# PIC_Schematic.net
KiCad netlist of a schematic drawn in Altium Designer
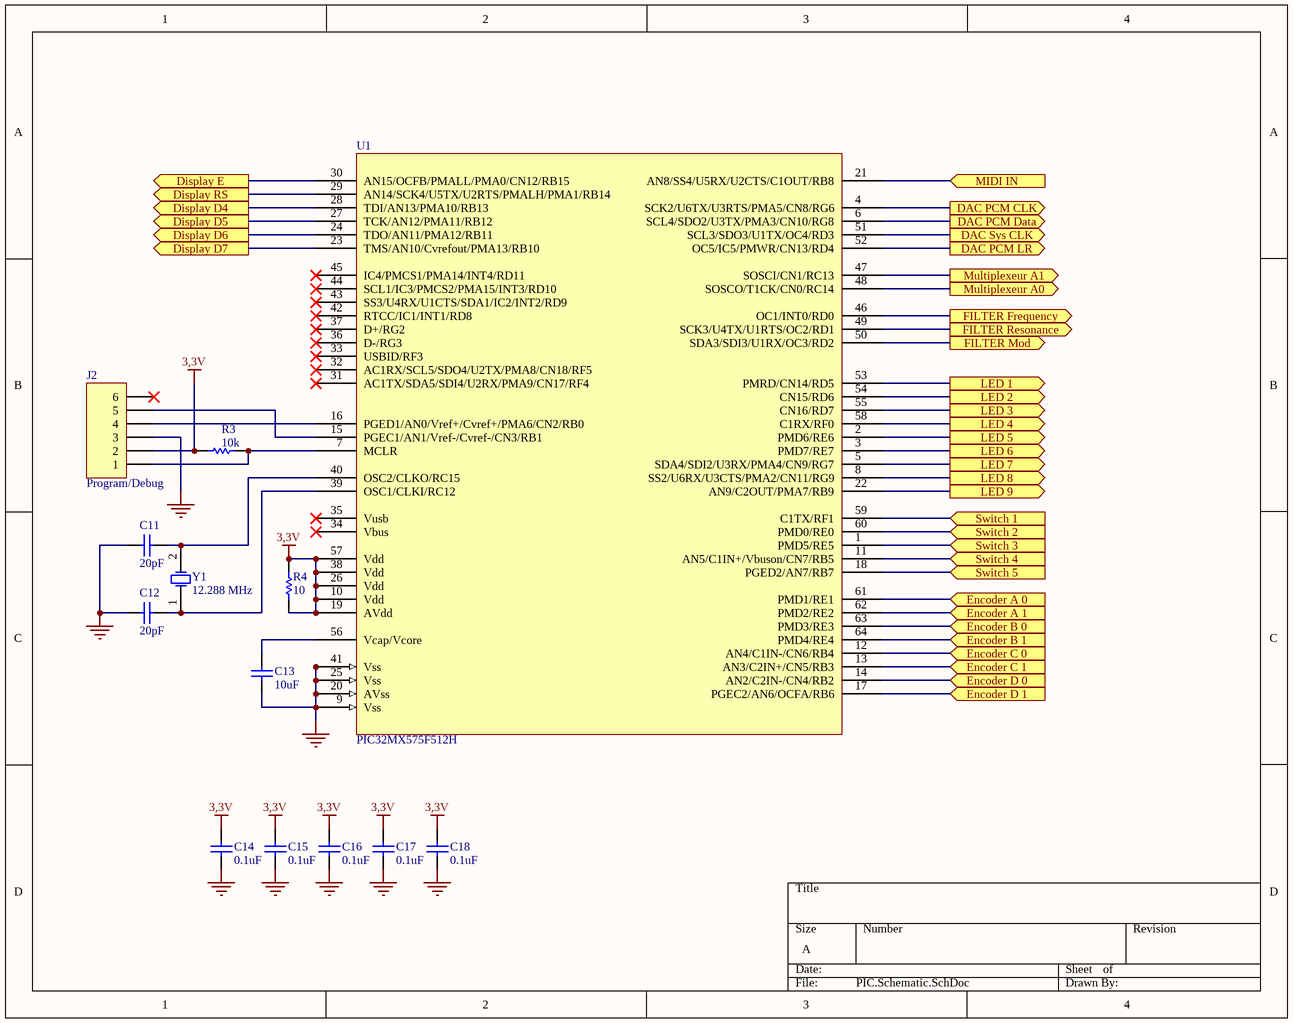
[diagram p0: PIC.Schematic.SchDoc]

(export (version "E")
  (design (tool "Eeschema 10.0.6"))
  (components
    (comp (ref "C11")
      (value "20pF")
      (footprint "CAPC1608N")
      (description "Capacitor (Semiconductor SIM Model)")
      (fields (field (name "PUBLISHER") "Altium Limited"))
      (libsource (lib "Miscellaneous Devices") (part "Cap Semi"))
    )
    (comp (ref "C12")
      (value "20pF")
      (footprint "CAPC1608N")
      (description "Capacitor (Semiconductor SIM Model)")
      (fields (field (name "PUBLISHER") "Altium Limited"))
      (libsource (lib "Miscellaneous Devices") (part "Cap Semi"))
    )
    (comp (ref "C13")
      (value "10uF")
      (footprint "RAD-0.3")
      (description "Capacitor")
      (fields (field (name "PUBLISHER") "Altium Limited"))
      (libsource (lib "Miscellaneous Devices") (part "Cap"))
    )
    (comp (ref "C14")
      (value "0.1uF")
      (footprint "CAPC1608N")
      (description "Capacitor (Semiconductor SIM Model)")
      (fields (field (name "PUBLISHER") "Altium Limited"))
      (libsource (lib "Miscellaneous Devices") (part "Cap Semi"))
    )
    (comp (ref "C15")
      (value "0.1uF")
      (footprint "CAPC1608N")
      (description "Capacitor (Semiconductor SIM Model)")
      (fields (field (name "PUBLISHER") "Altium Limited"))
      (libsource (lib "Miscellaneous Devices") (part "Cap Semi"))
    )
    (comp (ref "C16")
      (value "0.1uF")
      (footprint "CAPC1608N")
      (description "Capacitor (Semiconductor SIM Model)")
      (fields (field (name "PUBLISHER") "Altium Limited"))
      (libsource (lib "Miscellaneous Devices") (part "Cap Semi"))
    )
    (comp (ref "C17")
      (value "0.1uF")
      (footprint "CAPC1608N")
      (description "Capacitor (Semiconductor SIM Model)")
      (fields (field (name "PUBLISHER") "Altium Limited"))
      (libsource (lib "Miscellaneous Devices") (part "Cap Semi"))
    )
    (comp (ref "C18")
      (value "0.1uF")
      (footprint "CAPC1608N")
      (description "Capacitor (Semiconductor SIM Model)")
      (fields (field (name "PUBLISHER") "Altium Limited"))
      (libsource (lib "Miscellaneous Devices") (part "Cap Semi"))
    )
    (comp (ref "J2")
      (value "Program/Debug")
      (footprint "RJ11")
      (description "Header, 6-Pin, Right Angle")
      (fields (field (name "PUBLISHER") "Altium Limited"))
      (libsource (lib "Miscellaneous Connectors") (part "Header 6H"))
    )
    (comp (ref "R3")
      (value "10k")
      (footprint "CAPC1608N")
      (description "Resistor")
      (fields (field (name "PUBLISHER") "Altium Limited"))
      (libsource (lib "Miscellaneous Devices") (part "Res1"))
    )
    (comp (ref "R4")
      (value "10")
      (footprint "CAPC1608N")
      (description "Resistor")
      (fields (field (name "PUBLISHER") "Altium Limited"))
      (libsource (lib "Miscellaneous Devices") (part "Res1"))
    )
    (comp (ref "U1")
      (value "PIC32MX575F512H")
      (footprint "PIC32")
      (libsource (lib "SynthyTwo.Components") (part "PIC32 MX575F512H"))
    )
    (comp (ref "Y1")
      (value "12.288 MHz")
      (footprint "Xtal")
      (description "Crystal Oscillator")
      (fields (field (name "PUBLISHER") "Altium Limited"))
      (libsource (lib "Miscellaneous Devices") (part "XTAL"))
    )
  )
  (nets
    (net (code "1") (name "/DAC PCM CLK") (class "Default")
      (node (ref "U1") (pin "4") (pinfunction "SCK2/U6TX/U3RTS/PMA5/CN8/RG6_4") (pintype "passive"))
    )
    (net (code "2") (name "/DAC PCM Data") (class "Default")
      (node (ref "U1") (pin "6") (pinfunction "SCL4/SDO2/U3TX/PMA3/CN10/RG8_6") (pintype "passive"))
    )
    (net (code "3") (name "/DAC PCM LR") (class "Default")
      (node (ref "U1") (pin "52") (pinfunction "OC5/IC5/PMWR/CN13/RD4_52") (pintype "passive"))
    )
    (net (code "4") (name "/DAC Sys CLK") (class "Default")
      (node (ref "U1") (pin "51") (pinfunction "SCL3/SDO3/U1TX/OC4/RD3_51") (pintype "passive"))
    )
    (net (code "5") (name "/Display D4") (class "Default")
      (node (ref "U1") (pin "28") (pinfunction "TDI/AN13/PMA10/RB13_28") (pintype "passive"))
    )
    (net (code "6") (name "/Display D5") (class "Default")
      (node (ref "U1") (pin "27") (pinfunction "TCK/AN12/PMA11/RB12_27") (pintype "passive"))
    )
    (net (code "7") (name "/Display D6") (class "Default")
      (node (ref "U1") (pin "24") (pinfunction "TDO/AN11/PMA12/RB11_24") (pintype "passive"))
    )
    (net (code "8") (name "/Display D7") (class "Default")
      (node (ref "U1") (pin "23") (pinfunction "TMS/AN10/Cvrefout/PMA13/RB10_23") (pintype "passive"))
    )
    (net (code "9") (name "/Display E") (class "Default")
      (node (ref "U1") (pin "30") (pinfunction "AN15/OCFB/PMALL/PMA0/CN12/RB15_30") (pintype "passive"))
    )
    (net (code "10") (name "/Display RS") (class "Default")
      (node (ref "U1") (pin "29") (pinfunction "AN14/SCK4/U5TX/U2RTS/PMALH/PMA1/RB14_29") (pintype "passive"))
    )
    (net (code "11") (name "/Encoder A 0") (class "Default")
      (node (ref "U1") (pin "61") (pinfunction "PMD1/RE1_61") (pintype "passive"))
    )
    (net (code "12") (name "/Encoder A 1") (class "Default")
      (node (ref "U1") (pin "62") (pinfunction "PMD2/RE2_62") (pintype "passive"))
    )
    (net (code "13") (name "/Encoder B 0") (class "Default")
      (node (ref "U1") (pin "63") (pinfunction "PMD3/RE3_63") (pintype "passive"))
    )
    (net (code "14") (name "/Encoder B 1") (class "Default")
      (node (ref "U1") (pin "64") (pinfunction "PMD4/RE4_64") (pintype "passive"))
    )
    (net (code "15") (name "/Encoder C 0") (class "Default")
      (node (ref "U1") (pin "12") (pinfunction "AN4/C1IN-/CN6/RB4_12") (pintype "passive"))
    )
    (net (code "16") (name "/Encoder C 1") (class "Default")
      (node (ref "U1") (pin "13") (pinfunction "AN3/C2IN+/CN5/RB3_13") (pintype "passive"))
    )
    (net (code "17") (name "/Encoder D 0") (class "Default")
      (node (ref "U1") (pin "14") (pinfunction "AN2/C2IN-/CN4/RB2_14") (pintype "passive"))
    )
    (net (code "18") (name "/Encoder D 1") (class "Default")
      (node (ref "U1") (pin "17") (pinfunction "PGEC2/AN6/OCFA/RB6_17") (pintype "passive"))
    )
    (net (code "19") (name "/FILTER Frequency") (class "Default")
      (node (ref "U1") (pin "46") (pinfunction "OC1/INT0/RD0_46") (pintype "passive"))
    )
    (net (code "20") (name "/FILTER Mod") (class "Default")
      (node (ref "U1") (pin "50") (pinfunction "SDA3/SDI3/U1RX/OC3/RD2_50") (pintype "passive"))
    )
    (net (code "21") (name "/FILTER Resonance") (class "Default")
      (node (ref "U1") (pin "49") (pinfunction "SCK3/U4TX/U1RTS/OC2/RD1_49") (pintype "passive"))
    )
    (net (code "22") (name "/LED 1") (class "Default")
      (node (ref "U1") (pin "53") (pinfunction "PMRD/CN14/RD5_53") (pintype "passive"))
    )
    (net (code "23") (name "/LED 2") (class "Default")
      (node (ref "U1") (pin "54") (pinfunction "CN15/RD6_54") (pintype "passive"))
    )
    (net (code "24") (name "/LED 3") (class "Default")
      (node (ref "U1") (pin "55") (pinfunction "CN16/RD7_55") (pintype "passive"))
    )
    (net (code "25") (name "/LED 4") (class "Default")
      (node (ref "U1") (pin "58") (pinfunction "C1RX/RF0_58") (pintype "passive"))
    )
    (net (code "26") (name "/LED 5") (class "Default")
      (node (ref "U1") (pin "2") (pinfunction "PMD6/RE6_2") (pintype "passive"))
    )
    (net (code "27") (name "/LED 6") (class "Default")
      (node (ref "U1") (pin "3") (pinfunction "PMD7/RE7_3") (pintype "passive"))
    )
    (net (code "28") (name "/LED 7") (class "Default")
      (node (ref "U1") (pin "5") (pinfunction "SDA4/SDI2/U3RX/PMA4/CN9/RG7_5") (pintype "passive"))
    )
    (net (code "29") (name "/LED 8") (class "Default")
      (node (ref "U1") (pin "8") (pinfunction "SS2/U6RX/U3CTS/PMA2/CN11/RG9_8") (pintype "passive"))
    )
    (net (code "30") (name "/LED 9") (class "Default")
      (node (ref "U1") (pin "22") (pinfunction "AN9/C2OUT/PMA7/RB9_22") (pintype "passive"))
    )
    (net (code "31") (name "/MIDI IN") (class "Default")
      (node (ref "U1") (pin "21") (pinfunction "AN8/SS4/U5RX/U2CTS/C1OUT/RB8_21") (pintype "passive"))
    )
    (net (code "32") (name "/Multiplexeur A0") (class "Default")
      (node (ref "U1") (pin "48") (pinfunction "SOSCO/T1CK/CN0/RC14_48") (pintype "passive"))
    )
    (net (code "33") (name "/Multiplexeur A1") (class "Default")
      (node (ref "U1") (pin "47") (pinfunction "SOSCI/CN1/RC13_47") (pintype "passive"))
    )
    (net (code "34") (name "/Switch 1") (class "Default")
      (node (ref "U1") (pin "59") (pinfunction "C1TX/RF1_59") (pintype "passive"))
    )
    (net (code "35") (name "/Switch 2") (class "Default")
      (node (ref "U1") (pin "60") (pinfunction "PMD0/RE0_60") (pintype "passive"))
    )
    (net (code "36") (name "/Switch 3") (class "Default")
      (node (ref "U1") (pin "1") (pinfunction "PMD5/RE5_1") (pintype "passive"))
    )
    (net (code "37") (name "/Switch 4") (class "Default")
      (node (ref "U1") (pin "11") (pinfunction "AN5/C1IN+/Vbuson/CN7/RB5_11") (pintype "passive"))
    )
    (net (code "38") (name "/Switch 5") (class "Default")
      (node (ref "U1") (pin "18") (pinfunction "PGED2/AN7/RB7_18") (pintype "passive"))
    )
    (net (code "39") (name "3,3V") (class "Default")
      (node (ref "C14") (pin "2") (pinfunction "2_2") (pintype "passive"))
      (node (ref "C15") (pin "2") (pinfunction "2_2") (pintype "passive"))
      (node (ref "C16") (pin "2") (pinfunction "2_2") (pintype "passive"))
      (node (ref "C17") (pin "2") (pinfunction "2_2") (pintype "passive"))
      (node (ref "C18") (pin "2") (pinfunction "2_2") (pintype "passive"))
      (node (ref "J2") (pin "2") (pinfunction "2_2") (pintype "passive"))
      (node (ref "R3") (pin "2") (pinfunction "2_2") (pintype "passive"))
      (node (ref "R4") (pin "1") (pinfunction "1_1") (pintype "passive"))
      (node (ref "R4") (pin "2") (pinfunction "2_2") (pintype "passive"))
      (node (ref "U1") (pin "10") (pinfunction "Vdd_10") (pintype "passive"))
      (node (ref "U1") (pin "19") (pinfunction "AVdd_19") (pintype "passive"))
      (node (ref "U1") (pin "26") (pinfunction "Vdd_26") (pintype "passive"))
      (node (ref "U1") (pin "38") (pinfunction "Vdd_38") (pintype "passive"))
      (node (ref "U1") (pin "57") (pinfunction "Vdd_57") (pintype "passive"))
    )
    (net (code "40") (name "GND") (class "Default")
      (node (ref "C11") (pin "1") (pinfunction "1_1") (pintype "passive"))
      (node (ref "C12") (pin "1") (pinfunction "1_1") (pintype "passive"))
      (node (ref "C13") (pin "1") (pinfunction "1_1") (pintype "passive"))
      (node (ref "C14") (pin "1") (pinfunction "1_1") (pintype "passive"))
      (node (ref "C15") (pin "1") (pinfunction "1_1") (pintype "passive"))
      (node (ref "C16") (pin "1") (pinfunction "1_1") (pintype "passive"))
      (node (ref "C17") (pin "1") (pinfunction "1_1") (pintype "passive"))
      (node (ref "C18") (pin "1") (pinfunction "1_1") (pintype "passive"))
      (node (ref "J2") (pin "3") (pinfunction "3_3") (pintype "passive"))
      (node (ref "U1") (pin "20") (pinfunction "AVss_20") (pintype "input"))
      (node (ref "U1") (pin "25") (pinfunction "Vss_25") (pintype "input"))
      (node (ref "U1") (pin "41") (pinfunction "Vss_41") (pintype "input"))
      (node (ref "U1") (pin "9") (pinfunction "Vss_9") (pintype "input"))
    )
    (net (code "41") (name "Net-(U1-MCLR)") (class "Default")
      (node (ref "J2") (pin "1") (pinfunction "1_1") (pintype "passive"))
      (node (ref "R3") (pin "1") (pinfunction "1_1") (pintype "passive"))
      (node (ref "U1") (pin "7") (pinfunction "MCLR_7") (pintype "passive"))
    )
    (net (code "42") (name "Net-(U1-OSC1{slash}CLKI{slash}RC12)") (class "Default")
      (node (ref "C12") (pin "2") (pinfunction "2_2") (pintype "passive"))
      (node (ref "U1") (pin "39") (pinfunction "OSC1/CLKI/RC12_39") (pintype "passive"))
      (node (ref "Y1") (pin "1") (pinfunction "OSC1_1") (pintype "passive"))
    )
    (net (code "43") (name "Net-(U1-OSC2{slash}CLKO{slash}RC15)") (class "Default")
      (node (ref "C11") (pin "2") (pinfunction "2_2") (pintype "passive"))
      (node (ref "U1") (pin "40") (pinfunction "OSC2/CLKO/RC15_40") (pintype "passive"))
      (node (ref "Y1") (pin "2") (pinfunction "OSC2_2") (pintype "passive"))
    )
    (net (code "44") (name "Net-(U1-PGEC1{slash}AN1{slash}Vref-{slash}Cvref-{slash}CN3{slash}RB1)") (class "Default")
      (node (ref "J2") (pin "5") (pinfunction "5_5") (pintype "passive"))
      (node (ref "U1") (pin "15") (pinfunction "PGEC1/AN1/Vref-/Cvref-/CN3/RB1_15") (pintype "passive"))
    )
    (net (code "45") (name "Net-(U1-PGED1{slash}AN0{slash}Vref+{slash}Cvref+{slash}PMA6{slash}CN2{slash}RB0)") (class "Default")
      (node (ref "J2") (pin "4") (pinfunction "4_4") (pintype "passive"))
      (node (ref "U1") (pin "16") (pinfunction "PGED1/AN0/Vref+/Cvref+/PMA6/CN2/RB0_16") (pintype "passive"))
    )
    (net (code "46") (name "Net-(U1-Vcap{slash}Vcore)") (class "Default")
      (node (ref "C13") (pin "2") (pinfunction "2_2") (pintype "passive"))
      (node (ref "U1") (pin "56") (pinfunction "Vcap/Vcore_56") (pintype "passive"))
    )
    (net (code "47") (name "unconnected-(J2-Pad6)") (class "Default")
      (node (ref "J2") (pin "6") (pinfunction "6_6") (pintype "passive+no_connect"))
    )
    (net (code "48") (name "unconnected-(U1-AC1RX{slash}SCL5{slash}SDO4{slash}U2TX{slash}PMA8{slash}CN18{slash}RF5-Pad32)") (class "Default")
      (node (ref "U1") (pin "32") (pinfunction "AC1RX/SCL5/SDO4/U2TX/PMA8/CN18/RF5_32") (pintype "passive+no_connect"))
    )
    (net (code "49") (name "unconnected-(U1-AC1TX{slash}SDA5{slash}SDI4{slash}U2RX{slash}PMA9{slash}CN17{slash}RF4-Pad31)") (class "Default")
      (node (ref "U1") (pin "31") (pinfunction "AC1TX/SDA5/SDI4/U2RX/PMA9/CN17/RF4_31") (pintype "passive+no_connect"))
    )
    (net (code "50") (name "unconnected-(U1-D+{slash}RG2-Pad37)") (class "Default")
      (node (ref "U1") (pin "37") (pinfunction "D+/RG2_37") (pintype "passive+no_connect"))
    )
    (net (code "51") (name "unconnected-(U1-D-{slash}RG3-Pad36)") (class "Default")
      (node (ref "U1") (pin "36") (pinfunction "D-/RG3_36") (pintype "passive+no_connect"))
    )
    (net (code "52") (name "unconnected-(U1-IC4{slash}PMCS1{slash}PMA14{slash}INT4{slash}RD11-Pad45)") (class "Default")
      (node (ref "U1") (pin "45") (pinfunction "IC4/PMCS1/PMA14/INT4/RD11_45") (pintype "passive+no_connect"))
    )
    (net (code "53") (name "unconnected-(U1-RTCC{slash}IC1{slash}INT1{slash}RD8-Pad42)") (class "Default")
      (node (ref "U1") (pin "42") (pinfunction "RTCC/IC1/INT1/RD8_42") (pintype "passive+no_connect"))
    )
    (net (code "54") (name "unconnected-(U1-SCL1{slash}IC3{slash}PMCS2{slash}PMA15{slash}INT3{slash}RD10-Pad44)") (class "Default")
      (node (ref "U1") (pin "44") (pinfunction "SCL1/IC3/PMCS2/PMA15/INT3/RD10_44") (pintype "passive+no_connect"))
    )
    (net (code "55") (name "unconnected-(U1-SS3{slash}U4RX{slash}U1CTS{slash}SDA1{slash}IC2{slash}INT2{slash}RD9-Pad43)") (class "Default")
      (node (ref "U1") (pin "43") (pinfunction "SS3/U4RX/U1CTS/SDA1/IC2/INT2/RD9_43") (pintype "passive+no_connect"))
    )
    (net (code "56") (name "unconnected-(U1-USBID{slash}RF3-Pad33)") (class "Default")
      (node (ref "U1") (pin "33") (pinfunction "USBID/RF3_33") (pintype "passive+no_connect"))
    )
    (net (code "57") (name "unconnected-(U1-Vbus-Pad34)") (class "Default")
      (node (ref "U1") (pin "34") (pinfunction "Vbus_34") (pintype "passive+no_connect"))
    )
    (net (code "58") (name "unconnected-(U1-Vusb-Pad35)") (class "Default")
      (node (ref "U1") (pin "35") (pinfunction "Vusb_35") (pintype "passive+no_connect"))
    )
  )
)
